# MCU.net
KiCad netlist of a schematic drawn in Altium Designer
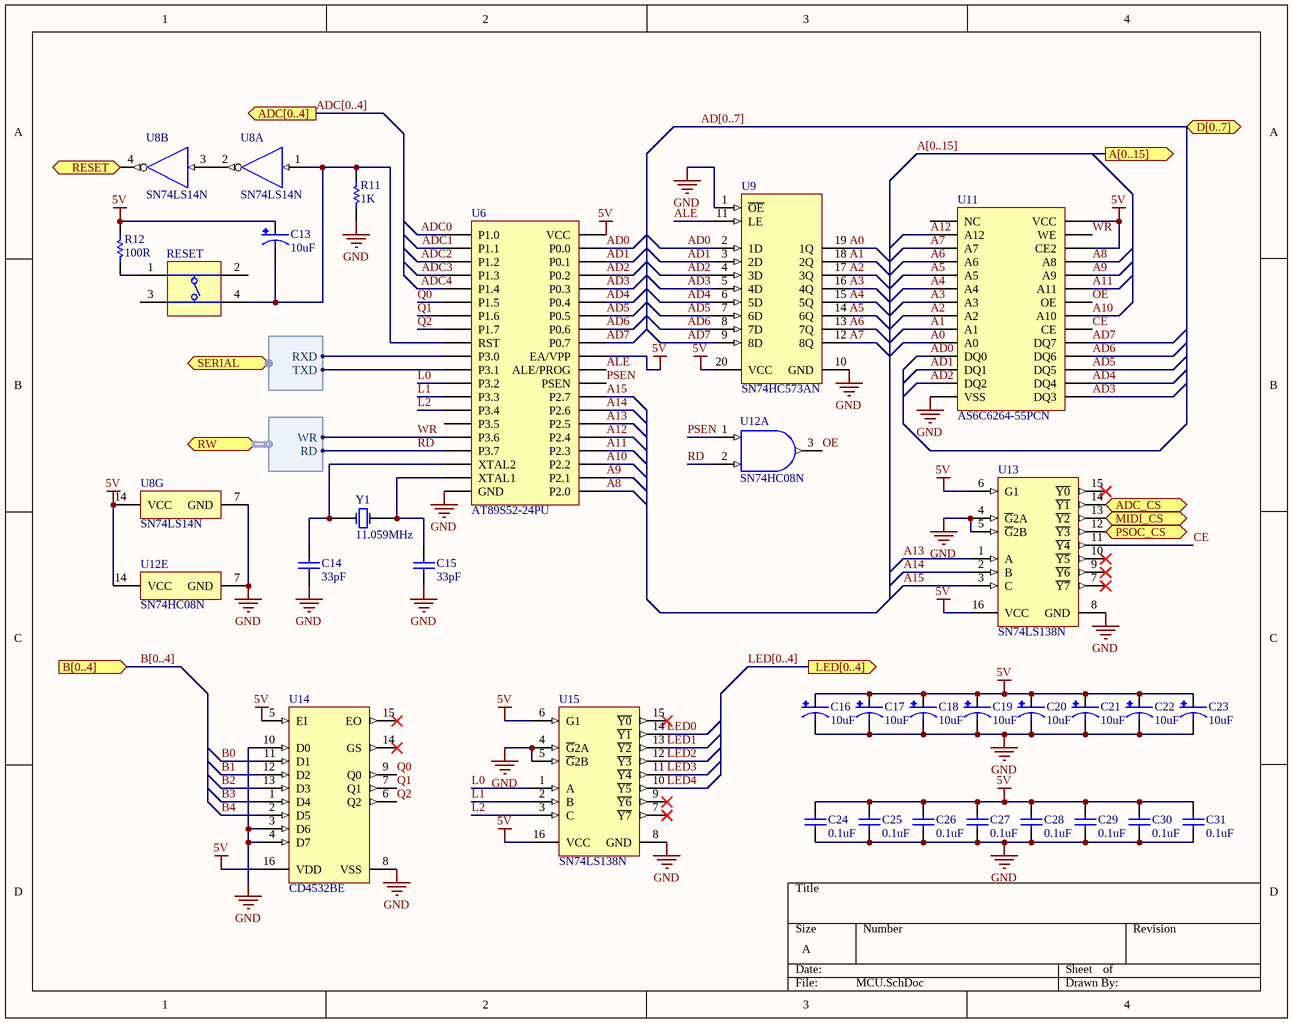
[diagram p0: MCU.SchDoc]

(export (version "E")
  (design (tool "Eeschema 10.0.6"))
  (components
    (comp (ref "C13")
      (value "10uF")
      (footprint "CPOL-RADIAL")
      (libsource (lib "Components") (part "PolarizedCap"))
    )
    (comp (ref "C14") (value "33pF") (footprint "CAP-PTH") (libsource (lib "Components") (part "Cap")))
    (comp (ref "C15") (value "33pF") (footprint "CAP-PTH") (libsource (lib "Components") (part "Cap")))
    (comp (ref "C16")
      (value "10uF")
      (footprint "CPOL-RADIAL")
      (libsource (lib "Components") (part "PolarizedCap"))
    )
    (comp (ref "C17")
      (value "10uF")
      (footprint "CPOL-RADIAL")
      (libsource (lib "Components") (part "PolarizedCap"))
    )
    (comp (ref "C18")
      (value "10uF")
      (footprint "CPOL-RADIAL")
      (libsource (lib "Components") (part "PolarizedCap"))
    )
    (comp (ref "C19")
      (value "10uF")
      (footprint "CPOL-RADIAL")
      (libsource (lib "Components") (part "PolarizedCap"))
    )
    (comp (ref "C20")
      (value "10uF")
      (footprint "CPOL-RADIAL")
      (libsource (lib "Components") (part "PolarizedCap"))
    )
    (comp (ref "C21")
      (value "10uF")
      (footprint "CPOL-RADIAL")
      (libsource (lib "Components") (part "PolarizedCap"))
    )
    (comp (ref "C22")
      (value "10uF")
      (footprint "CPOL-RADIAL")
      (libsource (lib "Components") (part "PolarizedCap"))
    )
    (comp (ref "C23")
      (value "10uF")
      (footprint "CPOL-RADIAL")
      (libsource (lib "Components") (part "PolarizedCap"))
    )
    (comp (ref "C24") (value "0.1uF") (footprint "CAP-PTH") (libsource (lib "Components") (part "Cap")))
    (comp (ref "C25") (value "0.1uF") (footprint "CAP-PTH") (libsource (lib "Components") (part "Cap")))
    (comp (ref "C26") (value "0.1uF") (footprint "CAP-PTH") (libsource (lib "Components") (part "Cap")))
    (comp (ref "C27") (value "0.1uF") (footprint "CAP-PTH") (libsource (lib "Components") (part "Cap")))
    (comp (ref "C28") (value "0.1uF") (footprint "CAP-PTH") (libsource (lib "Components") (part "Cap")))
    (comp (ref "C29") (value "0.1uF") (footprint "CAP-PTH") (libsource (lib "Components") (part "Cap")))
    (comp (ref "C30") (value "0.1uF") (footprint "CAP-PTH") (libsource (lib "Components") (part "Cap")))
    (comp (ref "C31") (value "0.1uF") (footprint "CAP-PTH") (libsource (lib "Components") (part "Cap")))
    (comp (ref "R11") (value "1K") (footprint "RESISTOR") (libsource (lib "Components") (part "Resistor")))
    (comp (ref "R12") (value "100R") (footprint "RESISTOR") (libsource (lib "Components") (part "Resistor")))
    (comp (ref "RESET")
      (value "~")
      (footprint "TACTILE_SWITCH")
      (description "Switch, SPNO Push Button SMD")
      (libsource (lib "Components") (part "Switch"))
    )
    (comp (ref "U6")
      (value "AT89S52-24PU")
      (footprint "PDIP-40")
      (fields (field (name "MANUFACTURER") "Atmel"))
      (libsource (lib "ICs") (part "AT89S52-24PU"))
    )
    (comp (ref "U8")
      (value "SN74LS14N")
      (footprint "N0014A")
      (description "Hex schmitt-trigger inverters, N0014A, TUBE")
      (fields
        (field (name "MANUFACTURER") "Texas Instruments")
        (field (name "GENERIC PART NUMBER") "SN74LS14")
      )
      (libsource (lib "Altium Content Vault") (part "TI-CD_SNX4XXXXXX4X_19A-14"))
    )
    (comp (ref "U9")
      (value "SN74HC573AN")
      (footprint "N0020A")
      (description "Octal Transparent D-Type Latches With 3-State Outputs, N0020A, TUBE")
      (fields
        (field (name "MANUFACTURER") "Texas Instruments")
        (field (name "GENERIC PART NUMBER") "SN74HC573A")
      )
      (libsource (lib "Altium Content Vault") (part "TI-CD_SNX4XXXX573X-X-20"))
    )
    (comp (ref "U11")
      (value "AS6C6264-55PCN")
      (footprint "PDIP-28")
      (fields (field (name "MANUFACTURER") "Alliance Memory, Inc."))
      (libsource (lib "ICs") (part "AS6C6264-55PCN"))
    )
    (comp (ref "U12")
      (value "SN74HC08N")
      (footprint "N0014A")
      (description "Quadruple 2-Input Positive-AND Gates, N0014A, TUBE")
      (fields
        (field (name "GENERIC PART NUMBER") "SN74HC08")
        (field (name "MANUFACTURER") "Texas Instruments")
      )
      (libsource (lib "Altium Content Vault") (part "TI-AND-4-2IN-14"))
    )
    (comp (ref "U13")
      (value "SN74LS138N")
      (footprint "N0016A")
      (description "3-line to 8-line decoder / demultiplexer, N0016A, TUBE")
      (fields
        (field (name "GENERIC PART NUMBER") "SN74LS138")
        (field (name "MANUFACTURER") "Texas Instruments")
      )
      (libsource (lib "Altium Content Vault") (part "TI-SNX4XXXX138-16"))
    )
    (comp (ref "U14")
      (value "CD4532BE")
      (footprint "N0016A")
      (description "CMOS 8-Bit Priority Encoder, N0016A, TUBE")
      (fields
        (field (name "GENERIC PART NUMBER") "CD4532B")
        (field (name "MANUFACTURER") "Texas Instruments")
      )
      (libsource (lib "Altium Content Vault") (part "TI-CD4532B-16"))
    )
    (comp (ref "U15")
      (value "SN74LS138N")
      (footprint "N0016A")
      (description "3-line to 8-line decoder / demultiplexer, N0016A, TUBE")
      (fields
        (field (name "GENERIC PART NUMBER") "SN74LS138")
        (field (name "MANUFACTURER") "Texas Instruments")
      )
      (libsource (lib "Altium Content Vault") (part "TI-SNX4XXXX138-16"))
    )
    (comp (ref "Y1")
      (value "11.059MHz")
      (footprint "CRYSTAL_PTH")
      (libsource (lib "Components") (part "Crystal"))
    )
  )
  (nets
    (net (code "3") (name "/A0") (class "Default")
      (node (ref "U11") (pin "10") (pinfunction "A0_10") (pintype "passive"))
      (node (ref "U9") (pin "19") (pinfunction "1Q_19") (pintype "tri_state"))
    )
    (net (code "4") (name "/A1") (class "Default")
      (node (ref "U11") (pin "9") (pinfunction "A1_9") (pintype "passive"))
      (node (ref "U9") (pin "18") (pinfunction "2Q_18") (pintype "tri_state"))
    )
    (net (code "5") (name "/A2") (class "Default")
      (node (ref "U11") (pin "8") (pinfunction "A2_8") (pintype "passive"))
      (node (ref "U9") (pin "17") (pinfunction "3Q_17") (pintype "tri_state"))
    )
    (net (code "6") (name "/A3") (class "Default")
      (node (ref "U11") (pin "7") (pinfunction "A3_7") (pintype "passive"))
      (node (ref "U9") (pin "16") (pinfunction "4Q_16") (pintype "tri_state"))
    )
    (net (code "7") (name "/A4") (class "Default")
      (node (ref "U11") (pin "6") (pinfunction "A4_6") (pintype "passive"))
      (node (ref "U9") (pin "15") (pinfunction "5Q_15") (pintype "tri_state"))
    )
    (net (code "8") (name "/A5") (class "Default")
      (node (ref "U11") (pin "5") (pinfunction "A5_5") (pintype "passive"))
      (node (ref "U9") (pin "14") (pinfunction "6Q_14") (pintype "tri_state"))
    )
    (net (code "9") (name "/A6") (class "Default")
      (node (ref "U11") (pin "4") (pinfunction "A6_4") (pintype "passive"))
      (node (ref "U9") (pin "13") (pinfunction "7Q_13") (pintype "tri_state"))
    )
    (net (code "10") (name "/A7") (class "Default")
      (node (ref "U11") (pin "3") (pinfunction "A7_3") (pintype "passive"))
      (node (ref "U9") (pin "12") (pinfunction "8Q_12") (pintype "tri_state"))
    )
    (net (code "11") (name "/A8") (class "Default")
      (node (ref "U11") (pin "25") (pinfunction "A8_25") (pintype "passive"))
      (node (ref "U6") (pin "21") (pinfunction "P2.0_21") (pintype "passive"))
    )
    (net (code "12") (name "/A9") (class "Default")
      (node (ref "U11") (pin "24") (pinfunction "A9_24") (pintype "passive"))
      (node (ref "U6") (pin "22") (pinfunction "P2.1_22") (pintype "passive"))
    )
    (net (code "13") (name "/A10") (class "Default")
      (node (ref "U11") (pin "21") (pinfunction "A10_21") (pintype "passive"))
      (node (ref "U6") (pin "23") (pinfunction "P2.2_23") (pintype "passive"))
    )
    (net (code "14") (name "/A11") (class "Default")
      (node (ref "U11") (pin "23") (pinfunction "A11_23") (pintype "passive"))
      (node (ref "U6") (pin "24") (pinfunction "P2.3_24") (pintype "passive"))
    )
    (net (code "15") (name "/A12") (class "Default")
      (node (ref "U11") (pin "2") (pinfunction "A12_2") (pintype "passive"))
      (node (ref "U6") (pin "25") (pinfunction "P2.4_25") (pintype "passive"))
    )
    (net (code "16") (name "/A13") (class "Default")
      (node (ref "U13") (pin "1") (pinfunction "A_1") (pintype "input"))
      (node (ref "U6") (pin "26") (pinfunction "P2.5_26") (pintype "passive"))
    )
    (net (code "17") (name "/A14") (class "Default")
      (node (ref "U13") (pin "2") (pinfunction "B_2") (pintype "input"))
      (node (ref "U6") (pin "27") (pinfunction "P2.6_27") (pintype "passive"))
    )
    (net (code "18") (name "/A15") (class "Default")
      (node (ref "U13") (pin "3") (pinfunction "C_3") (pintype "input"))
      (node (ref "U6") (pin "28") (pinfunction "P2.7_28") (pintype "passive"))
    )
    (net (code "19") (name "/AD0") (class "Default")
      (node (ref "U11") (pin "11") (pinfunction "DQ0_11") (pintype "passive"))
      (node (ref "U6") (pin "39") (pinfunction "P0.0_39") (pintype "passive"))
      (node (ref "U9") (pin "2") (pinfunction "1D_2") (pintype "input"))
    )
    (net (code "20") (name "/AD1") (class "Default")
      (node (ref "U11") (pin "12") (pinfunction "DQ1_12") (pintype "passive"))
      (node (ref "U6") (pin "38") (pinfunction "P0.1_38") (pintype "passive"))
      (node (ref "U9") (pin "3") (pinfunction "2D_3") (pintype "input"))
    )
    (net (code "21") (name "/AD2") (class "Default")
      (node (ref "U11") (pin "13") (pinfunction "DQ2_13") (pintype "passive"))
      (node (ref "U6") (pin "37") (pinfunction "P0.2_37") (pintype "passive"))
      (node (ref "U9") (pin "4") (pinfunction "3D_4") (pintype "input"))
    )
    (net (code "22") (name "/AD3") (class "Default")
      (node (ref "U11") (pin "15") (pinfunction "DQ3_15") (pintype "passive"))
      (node (ref "U6") (pin "36") (pinfunction "P0.3_36") (pintype "passive"))
      (node (ref "U9") (pin "5") (pinfunction "4D_5") (pintype "input"))
    )
    (net (code "23") (name "/AD4") (class "Default")
      (node (ref "U11") (pin "16") (pinfunction "DQ4_16") (pintype "passive"))
      (node (ref "U6") (pin "35") (pinfunction "P0.4_35") (pintype "passive"))
      (node (ref "U9") (pin "6") (pinfunction "5D_6") (pintype "input"))
    )
    (net (code "24") (name "/AD5") (class "Default")
      (node (ref "U11") (pin "17") (pinfunction "DQ5_17") (pintype "passive"))
      (node (ref "U6") (pin "34") (pinfunction "P0.5_34") (pintype "passive"))
      (node (ref "U9") (pin "7") (pinfunction "6D_7") (pintype "input"))
    )
    (net (code "25") (name "/AD6") (class "Default")
      (node (ref "U11") (pin "18") (pinfunction "DQ6_18") (pintype "passive"))
      (node (ref "U6") (pin "33") (pinfunction "P0.6_33") (pintype "passive"))
      (node (ref "U9") (pin "8") (pinfunction "7D_8") (pintype "input"))
    )
    (net (code "26") (name "/AD7") (class "Default")
      (node (ref "U11") (pin "19") (pinfunction "DQ7_19") (pintype "passive"))
      (node (ref "U6") (pin "32") (pinfunction "P0.7_32") (pintype "passive"))
      (node (ref "U9") (pin "9") (pinfunction "8D_9") (pintype "input"))
    )
    (net (code "27") (name "/ADC0") (class "Default")
      (node (ref "U6") (pin "1") (pinfunction "P1.0_1") (pintype "passive"))
    )
    (net (code "28") (name "/ADC1") (class "Default")
      (node (ref "U6") (pin "2") (pinfunction "P1.1_2") (pintype "passive"))
    )
    (net (code "29") (name "/ADC2") (class "Default")
      (node (ref "U6") (pin "3") (pinfunction "P1.2_3") (pintype "passive"))
    )
    (net (code "30") (name "/ADC3") (class "Default")
      (node (ref "U6") (pin "4") (pinfunction "P1.3_4") (pintype "passive"))
    )
    (net (code "31") (name "/ADC4") (class "Default")
      (node (ref "U6") (pin "5") (pinfunction "P1.4_5") (pintype "passive"))
    )
    (net (code "33") (name "/ADC_CS") (class "Default")
      (node (ref "U13") (pin "14") (pinfunction "~{Y1}_14") (pintype "output"))
    )
    (net (code "35") (name "/ALE") (class "Default")
      (node (ref "U6") (pin "30") (pinfunction "ALE/PROG_30") (pintype "passive"))
      (node (ref "U9") (pin "11") (pinfunction "LE_11") (pintype "input"))
    )
    (net (code "37") (name "/B0") (class "Default")
      (node (ref "U14") (pin "11") (pinfunction "D1_11") (pintype "input"))
    )
    (net (code "38") (name "/B1") (class "Default")
      (node (ref "U14") (pin "12") (pinfunction "D2_12") (pintype "input"))
    )
    (net (code "39") (name "/B2") (class "Default")
      (node (ref "U14") (pin "13") (pinfunction "D3_13") (pintype "input"))
    )
    (net (code "40") (name "/B3") (class "Default")
      (node (ref "U14") (pin "1") (pinfunction "D4_1") (pintype "input"))
    )
    (net (code "41") (name "/B4") (class "Default")
      (node (ref "U14") (pin "2") (pinfunction "D5_2") (pintype "input"))
    )
    (net (code "43") (name "/CE") (class "Default")
      (node (ref "U11") (pin "20") (pinfunction "CE_20") (pintype "passive"))
      (node (ref "U13") (pin "11") (pinfunction "~{Y4}_11") (pintype "output"))
    )
    (net (code "44") (name "/L0") (class "Default")
      (node (ref "U15") (pin "1") (pinfunction "A_1") (pintype "input"))
      (node (ref "U6") (pin "12") (pinfunction "P3.2_12") (pintype "passive"))
    )
    (net (code "45") (name "/L1") (class "Default")
      (node (ref "U15") (pin "2") (pinfunction "B_2") (pintype "input"))
      (node (ref "U6") (pin "13") (pinfunction "P3.3_13") (pintype "passive"))
    )
    (net (code "46") (name "/L2") (class "Default")
      (node (ref "U15") (pin "3") (pinfunction "C_3") (pintype "input"))
      (node (ref "U6") (pin "14") (pinfunction "P3.4_14") (pintype "passive"))
    )
    (net (code "47") (name "/LED0") (class "Default")
      (node (ref "U15") (pin "14") (pinfunction "~{Y1}_14") (pintype "output"))
    )
    (net (code "48") (name "/LED1") (class "Default")
      (node (ref "U15") (pin "13") (pinfunction "~{Y2}_13") (pintype "output"))
    )
    (net (code "49") (name "/LED2") (class "Default")
      (node (ref "U15") (pin "12") (pinfunction "~{Y3}_12") (pintype "output"))
    )
    (net (code "50") (name "/LED3") (class "Default")
      (node (ref "U15") (pin "11") (pinfunction "~{Y4}_11") (pintype "output"))
    )
    (net (code "51") (name "/LED4") (class "Default")
      (node (ref "U15") (pin "10") (pinfunction "~{Y5}_10") (pintype "output"))
    )
    (net (code "53") (name "/MIDI_CS") (class "Default")
      (node (ref "U13") (pin "13") (pinfunction "~{Y2}_13") (pintype "output"))
    )
    (net (code "54") (name "/OE") (class "Default")
      (node (ref "U11") (pin "22") (pinfunction "OE_22") (pintype "passive"))
      (node (ref "U12") (pin "3") (pinfunction "1Y_3") (pintype "output"))
    )
    (net (code "55") (name "/PSEN") (class "Default")
      (node (ref "U12") (pin "1") (pinfunction "1A_1") (pintype "input"))
      (node (ref "U6") (pin "29") (pinfunction "PSEN_29") (pintype "passive"))
    )
    (net (code "56") (name "/PSOC_CS") (class "Default")
      (node (ref "U13") (pin "12") (pinfunction "~{Y3}_12") (pintype "output"))
    )
    (net (code "57") (name "/Q0") (class "Default")
      (node (ref "U14") (pin "9") (pinfunction "Q0_9") (pintype "output"))
      (node (ref "U6") (pin "6") (pinfunction "P1.5_6") (pintype "passive"))
    )
    (net (code "58") (name "/Q1") (class "Default")
      (node (ref "U14") (pin "7") (pinfunction "Q1_7") (pintype "output"))
      (node (ref "U6") (pin "7") (pinfunction "P1.6_7") (pintype "passive"))
    )
    (net (code "59") (name "/Q2") (class "Default")
      (node (ref "U14") (pin "6") (pinfunction "Q2_6") (pintype "output"))
      (node (ref "U6") (pin "8") (pinfunction "P1.7_8") (pintype "passive"))
    )
    (net (code "60") (name "/RD") (class "Default")
      (node (ref "U12") (pin "2") (pinfunction "1B_2") (pintype "input"))
      (node (ref "U6") (pin "17") (pinfunction "P3.7_17") (pintype "passive"))
    )
    (net (code "61") (name "/RESET") (class "Default")
      (node (ref "U8") (pin "4") (pinfunction "~{2Y}_4") (pintype "output"))
    )
    (net (code "62") (name "/RXD") (class "Default")
      (node (ref "U6") (pin "10") (pinfunction "P3.0_10") (pintype "passive"))
    )
    (net (code "63") (name "/TXD") (class "Default")
      (node (ref "U6") (pin "11") (pinfunction "P3.1_11") (pintype "passive"))
    )
    (net (code "64") (name "/WR") (class "Default")
      (node (ref "U11") (pin "27") (pinfunction "WE_27") (pintype "passive"))
      (node (ref "U6") (pin "16") (pinfunction "P3.6_16") (pintype "passive"))
    )
    (net (code "67") (name "5V") (class "Default")
      (node (ref "C13") (pin "1") (pinfunction "+_1") (pintype "passive"))
      (node (ref "C16") (pin "1") (pinfunction "+_1") (pintype "passive"))
      (node (ref "C17") (pin "1") (pinfunction "+_1") (pintype "passive"))
      (node (ref "C18") (pin "1") (pinfunction "+_1") (pintype "passive"))
      (node (ref "C19") (pin "1") (pinfunction "+_1") (pintype "passive"))
      (node (ref "C20") (pin "1") (pinfunction "+_1") (pintype "passive"))
      (node (ref "C21") (pin "1") (pinfunction "+_1") (pintype "passive"))
      (node (ref "C22") (pin "1") (pinfunction "+_1") (pintype "passive"))
      (node (ref "C23") (pin "1") (pinfunction "+_1") (pintype "passive"))
      (node (ref "C24") (pin "1") (pinfunction "1_1") (pintype "passive"))
      (node (ref "C25") (pin "1") (pinfunction "1_1") (pintype "passive"))
      (node (ref "C26") (pin "1") (pinfunction "1_1") (pintype "passive"))
      (node (ref "C27") (pin "1") (pinfunction "1_1") (pintype "passive"))
      (node (ref "C28") (pin "1") (pinfunction "1_1") (pintype "passive"))
      (node (ref "C29") (pin "1") (pinfunction "1_1") (pintype "passive"))
      (node (ref "C30") (pin "1") (pinfunction "1_1") (pintype "passive"))
      (node (ref "C31") (pin "1") (pinfunction "1_1") (pintype "passive"))
      (node (ref "R12") (pin "2") (pinfunction "2_2") (pintype "passive"))
      (node (ref "U11") (pin "26") (pinfunction "CE2_26") (pintype "passive"))
      (node (ref "U11") (pin "28") (pinfunction "VCC_28") (pintype "passive"))
      (node (ref "U12") (pin "14") (pinfunction "VCC_14") (pintype "power_in"))
      (node (ref "U13") (pin "16") (pinfunction "VCC_16") (pintype "power_in"))
      (node (ref "U13") (pin "6") (pinfunction "G1_6") (pintype "input"))
      (node (ref "U14") (pin "16") (pinfunction "VDD_16") (pintype "power_in"))
      (node (ref "U14") (pin "5") (pinfunction "EI_5") (pintype "input"))
      (node (ref "U15") (pin "16") (pinfunction "VCC_16") (pintype "power_in"))
      (node (ref "U15") (pin "6") (pinfunction "G1_6") (pintype "input"))
      (node (ref "U6") (pin "31") (pinfunction "EA/VPP_31") (pintype "passive"))
      (node (ref "U6") (pin "40") (pinfunction "VCC_40") (pintype "passive"))
      (node (ref "U8") (pin "14") (pinfunction "VCC_14") (pintype "power_in"))
      (node (ref "U9") (pin "20") (pinfunction "VCC_20") (pintype "power_in"))
    )
    (net (code "68") (name "GND") (class "Default")
      (node (ref "C14") (pin "2") (pinfunction "2_2") (pintype "passive"))
      (node (ref "C15") (pin "2") (pinfunction "2_2") (pintype "passive"))
      (node (ref "C16") (pin "2") (pinfunction "-_2") (pintype "passive"))
      (node (ref "C17") (pin "2") (pinfunction "-_2") (pintype "passive"))
      (node (ref "C18") (pin "2") (pinfunction "-_2") (pintype "passive"))
      (node (ref "C19") (pin "2") (pinfunction "-_2") (pintype "passive"))
      (node (ref "C20") (pin "2") (pinfunction "-_2") (pintype "passive"))
      (node (ref "C21") (pin "2") (pinfunction "-_2") (pintype "passive"))
      (node (ref "C22") (pin "2") (pinfunction "-_2") (pintype "passive"))
      (node (ref "C23") (pin "2") (pinfunction "-_2") (pintype "passive"))
      (node (ref "C24") (pin "2") (pinfunction "2_2") (pintype "passive"))
      (node (ref "C25") (pin "2") (pinfunction "2_2") (pintype "passive"))
      (node (ref "C26") (pin "2") (pinfunction "2_2") (pintype "passive"))
      (node (ref "C27") (pin "2") (pinfunction "2_2") (pintype "passive"))
      (node (ref "C28") (pin "2") (pinfunction "2_2") (pintype "passive"))
      (node (ref "C29") (pin "2") (pinfunction "2_2") (pintype "passive"))
      (node (ref "C30") (pin "2") (pinfunction "2_2") (pintype "passive"))
      (node (ref "C31") (pin "2") (pinfunction "2_2") (pintype "passive"))
      (node (ref "R11") (pin "1") (pinfunction "1_1") (pintype "passive"))
      (node (ref "U11") (pin "14") (pinfunction "VSS_14") (pintype "passive"))
      (node (ref "U12") (pin "7") (pinfunction "GND_7") (pintype "power_in"))
      (node (ref "U13") (pin "4") (pinfunction "~{G}2A_4") (pintype "input"))
      (node (ref "U13") (pin "5") (pinfunction "~{G}2B_5") (pintype "input"))
      (node (ref "U13") (pin "8") (pinfunction "GND_8") (pintype "power_in"))
      (node (ref "U14") (pin "10") (pinfunction "D0_10") (pintype "input"))
      (node (ref "U14") (pin "3") (pinfunction "D6_3") (pintype "input"))
      (node (ref "U14") (pin "4") (pinfunction "D7_4") (pintype "input"))
      (node (ref "U14") (pin "8") (pinfunction "VSS_8") (pintype "power_in"))
      (node (ref "U15") (pin "4") (pinfunction "~{G}2A_4") (pintype "input"))
      (node (ref "U15") (pin "5") (pinfunction "~{G}2B_5") (pintype "input"))
      (node (ref "U15") (pin "8") (pinfunction "GND_8") (pintype "power_in"))
      (node (ref "U6") (pin "20") (pinfunction "GND_20") (pintype "passive"))
      (node (ref "U8") (pin "7") (pinfunction "GND_7") (pintype "power_in"))
      (node (ref "U9") (pin "1") (pinfunction "~{OE}_1") (pintype "input"))
      (node (ref "U9") (pin "10") (pinfunction "GND_10") (pintype "power_in"))
    )
    (net (code "69") (name "Net-(C13--)") (class "Default")
      (node (ref "C13") (pin "2") (pinfunction "-_2") (pintype "passive"))
      (node (ref "R11") (pin "2") (pinfunction "2_2") (pintype "passive"))
      (node (ref "RESET") (pin "4") (pinfunction "T3_4") (pintype "passive"))
      (node (ref "U6") (pin "9") (pinfunction "RST_9") (pintype "passive"))
      (node (ref "U8") (pin "1") (pinfunction "1A_1") (pintype "input"))
    )
    (net (code "70") (name "Net-(RESET-T1)") (class "Default")
      (node (ref "R12") (pin "1") (pinfunction "1_1") (pintype "passive"))
      (node (ref "RESET") (pin "1") (pinfunction "T1_1") (pintype "passive"))
    )
    (net (code "71") (name "Net-(U6-XTAL1)") (class "Default")
      (node (ref "C15") (pin "1") (pinfunction "1_1") (pintype "passive"))
      (node (ref "U6") (pin "19") (pinfunction "XTAL1_19") (pintype "passive"))
      (node (ref "Y1") (pin "2") (pinfunction "X2_2") (pintype "passive"))
    )
    (net (code "72") (name "Net-(U6-XTAL2)") (class "Default")
      (node (ref "C14") (pin "1") (pinfunction "1_1") (pintype "passive"))
      (node (ref "U6") (pin "18") (pinfunction "XTAL2_18") (pintype "passive"))
      (node (ref "Y1") (pin "1") (pinfunction "X1_1") (pintype "passive"))
    )
    (net (code "73") (name "Net-(U8A-~{1Y})") (class "Default")
      (node (ref "U8") (pin "2") (pinfunction "~{1Y}_2") (pintype "output"))
      (node (ref "U8") (pin "3") (pinfunction "2A_3") (pintype "input"))
    )
    (net (code "74") (name "unconnected-(RESET-T2-Pad2)") (class "Default")
      (node (ref "RESET") (pin "2") (pinfunction "T2_2") (pintype "passive"))
    )
    (net (code "75") (name "unconnected-(RESET-T3-Pad3)") (class "Default")
      (node (ref "RESET") (pin "3") (pinfunction "T3_3") (pintype "passive"))
    )
    (net (code "76") (name "unconnected-(U6-P3.5-Pad15)") (class "Default")
      (node (ref "U6") (pin "15") (pinfunction "P3.5_15") (pintype "passive"))
    )
    (net (code "77") (name "unconnected-(U11-NC-Pad1)") (class "Default")
      (node (ref "U11") (pin "1") (pinfunction "NC_1") (pintype "passive"))
    )
    (net (code "78") (name "unconnected-(U13-~{Y0}-Pad15)") (class "Default")
      (node (ref "U13") (pin "15") (pinfunction "~{Y0}_15") (pintype "output+no_connect"))
    )
    (net (code "79") (name "unconnected-(U13-~{Y5}-Pad10)") (class "Default")
      (node (ref "U13") (pin "10") (pinfunction "~{Y5}_10") (pintype "output+no_connect"))
    )
    (net (code "80") (name "unconnected-(U13-~{Y6}-Pad9)") (class "Default")
      (node (ref "U13") (pin "9") (pinfunction "~{Y6}_9") (pintype "output+no_connect"))
    )
    (net (code "81") (name "unconnected-(U13-~{Y7}-Pad7)") (class "Default")
      (node (ref "U13") (pin "7") (pinfunction "~{Y7}_7") (pintype "output+no_connect"))
    )
    (net (code "82") (name "unconnected-(U14-EO-Pad15)") (class "Default")
      (node (ref "U14") (pin "15") (pinfunction "EO_15") (pintype "output+no_connect"))
    )
    (net (code "83") (name "unconnected-(U14-GS-Pad14)") (class "Default")
      (node (ref "U14") (pin "14") (pinfunction "GS_14") (pintype "output+no_connect"))
    )
    (net (code "84") (name "unconnected-(U15-~{Y0}-Pad15)") (class "Default")
      (node (ref "U15") (pin "15") (pinfunction "~{Y0}_15") (pintype "output+no_connect"))
    )
    (net (code "85") (name "unconnected-(U15-~{Y6}-Pad9)") (class "Default")
      (node (ref "U15") (pin "9") (pinfunction "~{Y6}_9") (pintype "output+no_connect"))
    )
    (net (code "86") (name "unconnected-(U15-~{Y7}-Pad7)") (class "Default")
      (node (ref "U15") (pin "7") (pinfunction "~{Y7}_7") (pintype "output+no_connect"))
    )
  )
)
